# ToF.net
KiCad netlist of a schematic drawn in Altium Designer
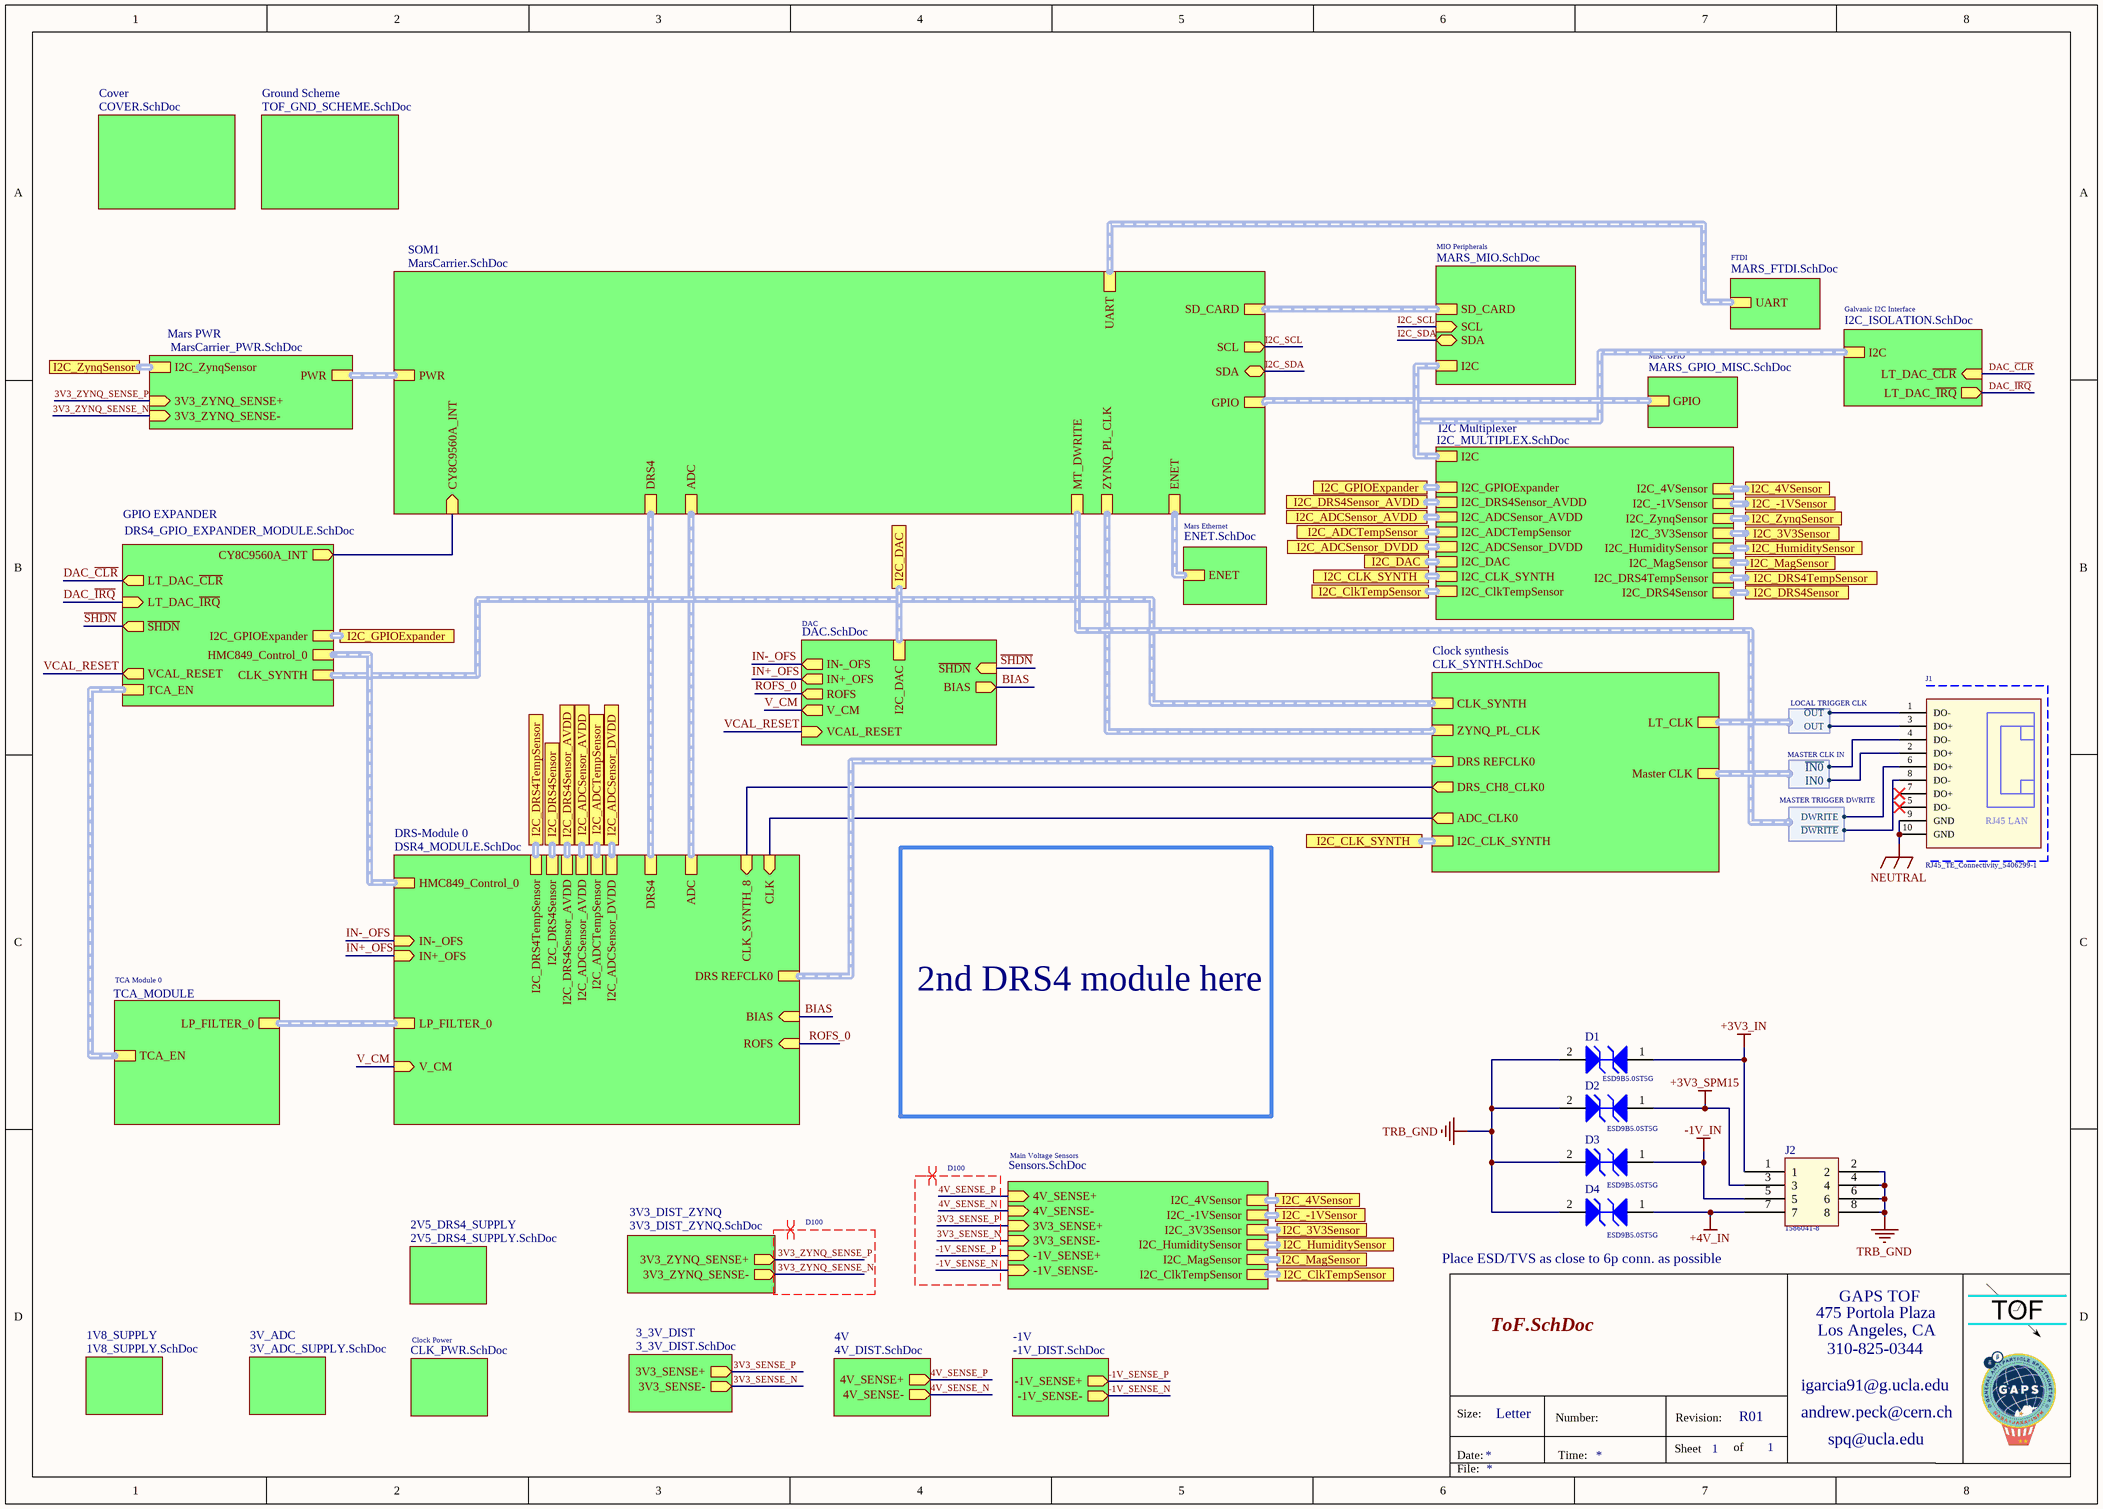
[diagram p0: ToF.SchDoc]

(export (version "E")
  (design (tool "Eeschema 10.0.6"))
  (components
    (comp (ref "D1")
      (value "ESD9B5.0ST5G")
      (footprint "ONSC-SOD-923-2-514AB-01_V")
      (fields (field (name "MANUFACTURER") "On Semiconductor"))
      (libsource (lib "On_Semiconductor_ESD9B5_0ST5G") (part "ESD9B5.0ST5G"))
    )
    (comp (ref "D2")
      (value "ESD9B5.0ST5G")
      (footprint "ONSC-SOD-923-2-514AB-01_V")
      (fields (field (name "MANUFACTURER") "On Semiconductor"))
      (libsource (lib "On_Semiconductor_ESD9B5_0ST5G") (part "ESD9B5.0ST5G"))
    )
    (comp (ref "D3")
      (value "ESD9B5.0ST5G")
      (footprint "ONSC-SOD-923-2-514AB-01_V")
      (fields (field (name "MANUFACTURER") "On Semiconductor"))
      (libsource (lib "On_Semiconductor_ESD9B5_0ST5G") (part "ESD9B5.0ST5G"))
    )
    (comp (ref "D4")
      (value "ESD9B5.0ST5G")
      (footprint "ONSC-SOD-923-2-514AB-01_V")
      (fields (field (name "MANUFACTURER") "On Semiconductor"))
      (libsource (lib "On_Semiconductor_ESD9B5_0ST5G") (part "ESD9B5.0ST5G"))
    )
    (comp (ref "J1")
      (value "RJ45_TE_Connectivity_5406299-1")
      (footprint "RJ45_TE_Connectivity_5406299-1:RJ45_TE_Connectivity_5406299-1")
      (description "Modular Connectors / Ethernet Connectors 1 PORT CAT 5")
      (libsource (lib "RJ45_TE_Connectivity_5406299-1") (part "RJ45_TE_Connectivity_5406299-1"))
    )
    (comp (ref "J2")
      (value "Header_TE_Connectivity_1586041-8_8POS")
      (footprint "Header_TE_Connectivity_1586041-8_8POS")
      (description "Headers & Wire Housings RA HDR W/O PEGS 8P")
      (fields (field (name "SERIES") "1586041-8"))
      (libsource (lib "Header_TE_Connectivity_1586041-8_8POS") (part "Header_TE_Connectivity_1586041-8_8POS"))
    )
  )
  (nets
    (net (code "70") (name "+3V3_IN") (class "Default")
      (node (ref "D1") (pin "1") (pinfunction "A1_1") (pintype "passive"))
      (node (ref "J2") (pin "1") (pinfunction "1_1") (pintype "passive"))
    )
    (net (code "71") (name "+3V3_SPM15") (class "Default")
      (node (ref "D2") (pin "1") (pinfunction "A1_1") (pintype "passive"))
      (node (ref "J2") (pin "3") (pinfunction "3_3") (pintype "passive"))
    )
    (net (code "72") (name "+4V_IN") (class "Default")
      (node (ref "D4") (pin "1") (pinfunction "A1_1") (pintype "passive"))
      (node (ref "J2") (pin "7") (pinfunction "7_7") (pintype "passive"))
    )
    (net (code "73") (name "-1V_IN") (class "Default")
      (node (ref "D3") (pin "1") (pinfunction "A1_1") (pintype "passive"))
      (node (ref "J2") (pin "5") (pinfunction "5_5") (pintype "passive"))
    )
    (net (code "92") (name "/DWRITE") (class "Default")
      (node (ref "J1") (pin "6") (pinfunction "DO+_6") (pintype "passive"))
    )
    (net (code "117") (name "/IN0") (class "Default")
      (node (ref "J1") (pin "2") (pinfunction "DO+_2") (pintype "passive"))
    )
    (net (code "119") (name "/OUT") (class "Default")
      (node (ref "J1") (pin "3") (pinfunction "DO+_3") (pintype "passive"))
    )
    (net (code "131") (name "/~{DWRITE}") (class "Default")
      (node (ref "J1") (pin "8") (pinfunction "DO-_8") (pintype "passive"))
    )
    (net (code "132") (name "/~{IN0}") (class "Default")
      (node (ref "J1") (pin "4") (pinfunction "DO-_4") (pintype "passive"))
    )
    (net (code "133") (name "/~{OUT}") (class "Default")
      (node (ref "J1") (pin "1") (pinfunction "DO-_1") (pintype "passive"))
    )
    (net (code "135") (name "NEUTRAL") (class "Default")
      (node (ref "J1") (pin "10") (pinfunction "GND_10") (pintype "passive"))
      (node (ref "J1") (pin "9") (pinfunction "GND_9") (pintype "passive"))
    )
    (net (code "136") (name "TRB_GND") (class "Default")
      (node (ref "D1") (pin "2") (pinfunction "A2_2") (pintype "passive"))
      (node (ref "D2") (pin "2") (pinfunction "A2_2") (pintype "passive"))
      (node (ref "D3") (pin "2") (pinfunction "A2_2") (pintype "passive"))
      (node (ref "D4") (pin "2") (pinfunction "A2_2") (pintype "passive"))
      (node (ref "J2") (pin "2") (pinfunction "2_2") (pintype "passive"))
      (node (ref "J2") (pin "4") (pinfunction "4_4") (pintype "passive"))
      (node (ref "J2") (pin "6") (pinfunction "6_6") (pintype "passive"))
      (node (ref "J2") (pin "8") (pinfunction "8_8") (pintype "passive"))
    )
    (net (code "137") (name "unconnected-(J1-DO+-Pad7)") (class "Default")
      (node (ref "J1") (pin "7") (pinfunction "DO+_7") (pintype "passive+no_connect"))
    )
    (net (code "138") (name "unconnected-(J1-DO--Pad5)") (class "Default")
      (node (ref "J1") (pin "5") (pinfunction "DO-_5") (pintype "passive+no_connect"))
    )
  )
)
